# Quantizer.net
KiCad netlist of a schematic drawn in Altium Designer
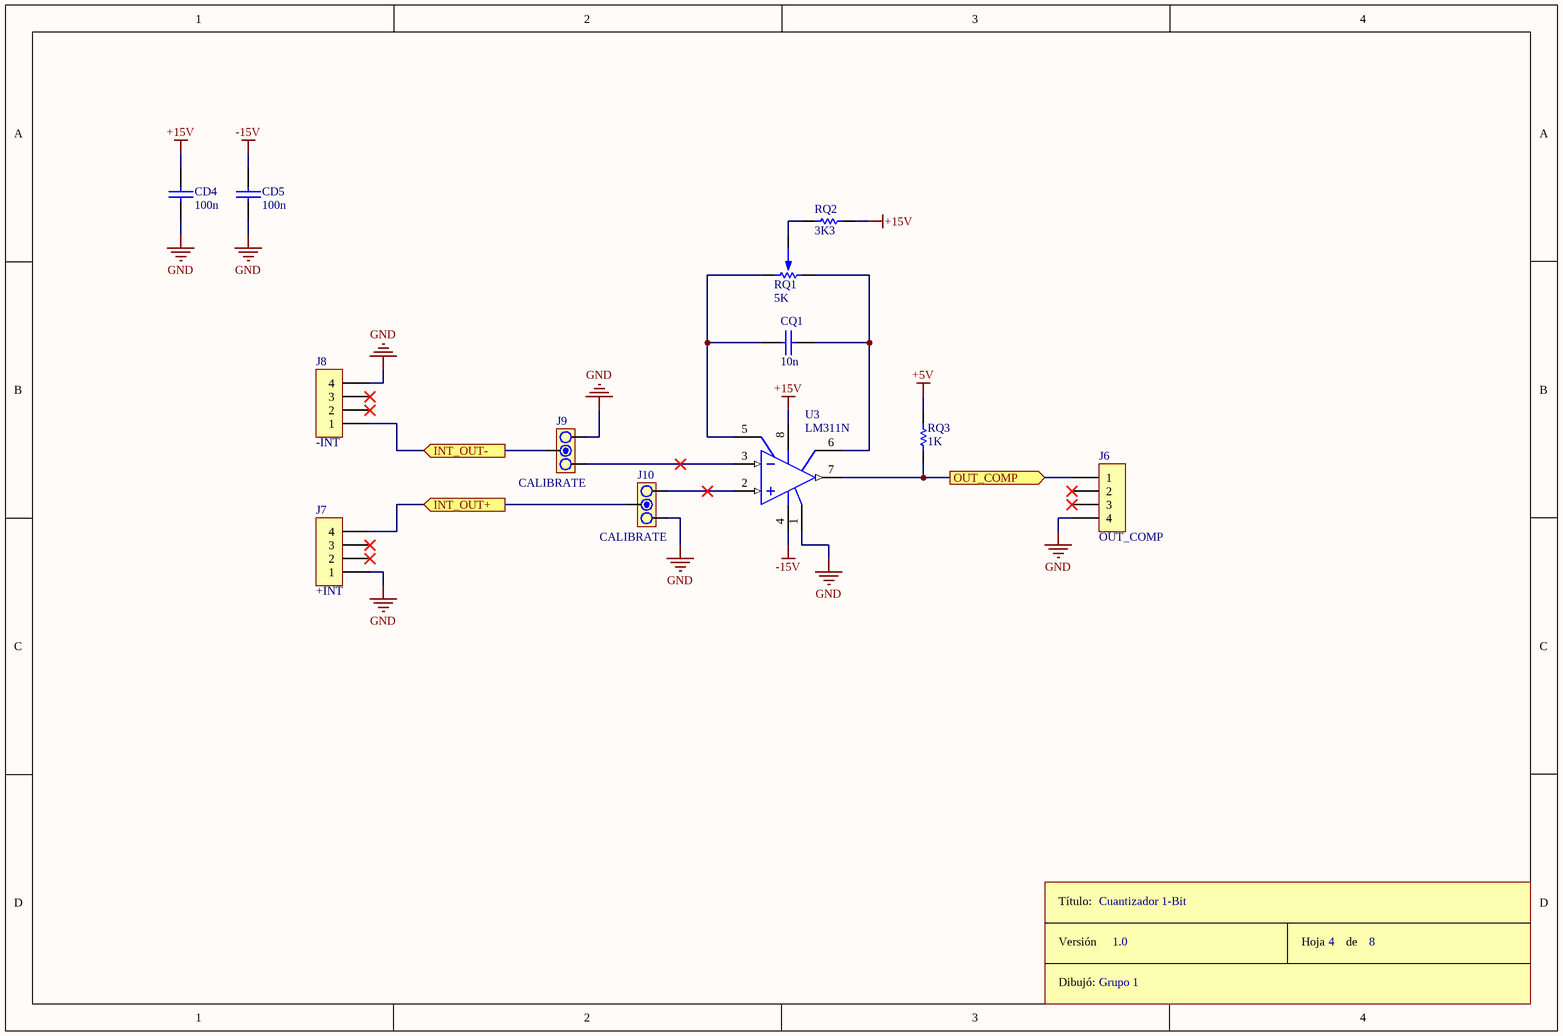
[diagram p0: Quantizer.SchDoc]

(export (version "E")
  (design (tool "Eeschema 10.0.6"))
  (components
    (comp (ref "CD4") (value "100n") (footprint "CAP100") (libsource (lib "LIBEBAL") (part "CAP")))
    (comp (ref "CD5") (value "100n") (footprint "CAP100") (libsource (lib "LIBEBAL") (part "CAP")))
    (comp (ref "CQ1") (value "10n") (footprint "CAP100") (libsource (lib "LIBEBAL") (part "CAP")))
    (comp (ref "J6") (value "OUT_COMP") (footprint "SIP4") (libsource (lib "") (part "CON4_1")))
    (comp (ref "J7") (value "+INT") (footprint "SIP4") (libsource (lib "LIBEBAL") (part "CON4")))
    (comp (ref "J8") (value "-INT") (footprint "SIP4") (libsource (lib "LIBEBAL") (part "CON4")))
    (comp (ref "J9") (value "CALIBRATE") (footprint "JUMPER3") (libsource (lib "LIBEBAL") (part "JUMPER3")))
    (comp (ref "J10") (value "CALIBRATE") (footprint "JUMPER3") (libsource (lib "LIBEBAL") (part "JUMPER3")))
    (comp (ref "ROT3") (value "Rótulo") (libsource (lib "LIB PIO IX") (part "Rótulo")))
    (comp (ref "RQ1") (value "5K") (footprint "PRESET V") (libsource (lib "LIBEBAL") (part "PRESET")))
    (comp (ref "RQ2") (value "3K3") (footprint "RES300") (libsource (lib "LIBEBAL") (part "RES")))
    (comp (ref "RQ3") (value "1K") (footprint "RES300") (libsource (lib "LIBEBAL") (part "RES")))
    (comp (ref "U3")
      (value "LM311N")
      (footprint "626-05")
      (description "High-Performance Voltage Comparator")
      (fields (field (name "PUBLISHER") "Altium Limited"))
      (libsource (lib "Motorola Analog Comparator") (part "LM311N"))
    )
  )
  (nets
    (net (code "1") (name "+5V") (class "Default")
      (node (ref "RQ3") (pin "2") (pinfunction "2_2") (pintype "passive"))
    )
    (net (code "2") (name "+15V") (class "Default")
      (node (ref "CD4") (pin "1") (pinfunction "1_1") (pintype "passive"))
      (node (ref "RQ2") (pin "2") (pinfunction "2_2") (pintype "passive"))
      (node (ref "U3") (pin "8") (pinfunction "V+_8") (pintype "power_in"))
    )
    (net (code "3") (name "-15V") (class "Default")
      (node (ref "CD5") (pin "1") (pinfunction "1_1") (pintype "passive"))
      (node (ref "U3") (pin "4") (pinfunction "V-_4") (pintype "power_in"))
    )
    (net (code "4") (name "/INT_OUT+") (class "Default")
      (node (ref "J10") (pin "2") (pinfunction "2_2") (pintype "passive"))
      (node (ref "J7") (pin "4") (pinfunction "4_4") (pintype "passive"))
    )
    (net (code "5") (name "/INT_OUT-") (class "Default")
      (node (ref "J8") (pin "1") (pinfunction "1_1") (pintype "passive"))
      (node (ref "J9") (pin "2") (pinfunction "2_2") (pintype "passive"))
    )
    (net (code "6") (name "/OUT_COMP") (class "Default")
      (node (ref "J6") (pin "1") (pinfunction "1_1") (pintype "passive"))
      (node (ref "RQ3") (pin "1") (pinfunction "1_1") (pintype "passive"))
      (node (ref "U3") (pin "7") (pinfunction "OUT_7") (pintype "output"))
    )
    (net (code "7") (name "GND") (class "Default")
      (node (ref "CD4") (pin "2") (pinfunction "2_2") (pintype "passive"))
      (node (ref "CD5") (pin "2") (pinfunction "2_2") (pintype "passive"))
      (node (ref "J10") (pin "3") (pinfunction "3_3") (pintype "passive"))
      (node (ref "J6") (pin "4") (pinfunction "4_4") (pintype "passive"))
      (node (ref "J7") (pin "1") (pinfunction "1_1") (pintype "passive"))
      (node (ref "J8") (pin "4") (pinfunction "4_4") (pintype "passive"))
      (node (ref "J9") (pin "1") (pinfunction "1_1") (pintype "passive"))
      (node (ref "U3") (pin "1") (pinfunction "GND_1") (pintype "power_in"))
    )
    (net (code "8") (name "Net-(RQ1-Pad2)") (class "Default")
      (node (ref "RQ1") (pin "2") (pinfunction "2_2") (pintype "passive"))
      (node (ref "RQ2") (pin "1") (pinfunction "1_1") (pintype "passive"))
    )
    (net (code "9") (name "Net-(U3-BAL)") (class "Default")
      (node (ref "CQ1") (pin "1") (pinfunction "1_1") (pintype "passive"))
      (node (ref "RQ1") (pin "1") (pinfunction "1_1") (pintype "passive"))
      (node (ref "U3") (pin "5") (pinfunction "BAL_5") (pintype "passive"))
    )
    (net (code "10") (name "Net-(U3-BAL{slash}STB)") (class "Default")
      (node (ref "CQ1") (pin "2") (pinfunction "2_2") (pintype "passive"))
      (node (ref "RQ1") (pin "3") (pinfunction "3_3") (pintype "passive"))
      (node (ref "U3") (pin "6") (pinfunction "BAL/STB_6") (pintype "passive"))
    )
    (net (code "11") (name "Net-(U3-IN+)") (class "Default")
      (node (ref "J10") (pin "1") (pinfunction "1_1") (pintype "passive"))
      (node (ref "U3") (pin "2") (pinfunction "IN+_2") (pintype "input"))
    )
    (net (code "12") (name "Net-(U3-IN-)") (class "Default")
      (node (ref "J9") (pin "3") (pinfunction "3_3") (pintype "passive"))
      (node (ref "U3") (pin "3") (pinfunction "IN-_3") (pintype "input"))
    )
    (net (code "13") (name "unconnected-(J6-Pad2)") (class "Default")
      (node (ref "J6") (pin "2") (pinfunction "2_2") (pintype "passive+no_connect"))
    )
    (net (code "14") (name "unconnected-(J6-Pad3)") (class "Default")
      (node (ref "J6") (pin "3") (pinfunction "3_3") (pintype "passive+no_connect"))
    )
    (net (code "15") (name "unconnected-(J7-Pad2)") (class "Default")
      (node (ref "J7") (pin "2") (pinfunction "2_2") (pintype "passive+no_connect"))
    )
    (net (code "16") (name "unconnected-(J7-Pad3)") (class "Default")
      (node (ref "J7") (pin "3") (pinfunction "3_3") (pintype "passive+no_connect"))
    )
    (net (code "17") (name "unconnected-(J8-Pad2)") (class "Default")
      (node (ref "J8") (pin "2") (pinfunction "2_2") (pintype "passive+no_connect"))
    )
    (net (code "18") (name "unconnected-(J8-Pad3)") (class "Default")
      (node (ref "J8") (pin "3") (pinfunction "3_3") (pintype "passive+no_connect"))
    )
  )
)
